# TPL5111_breakout.net
KiCad netlist of a schematic drawn in EAGLE
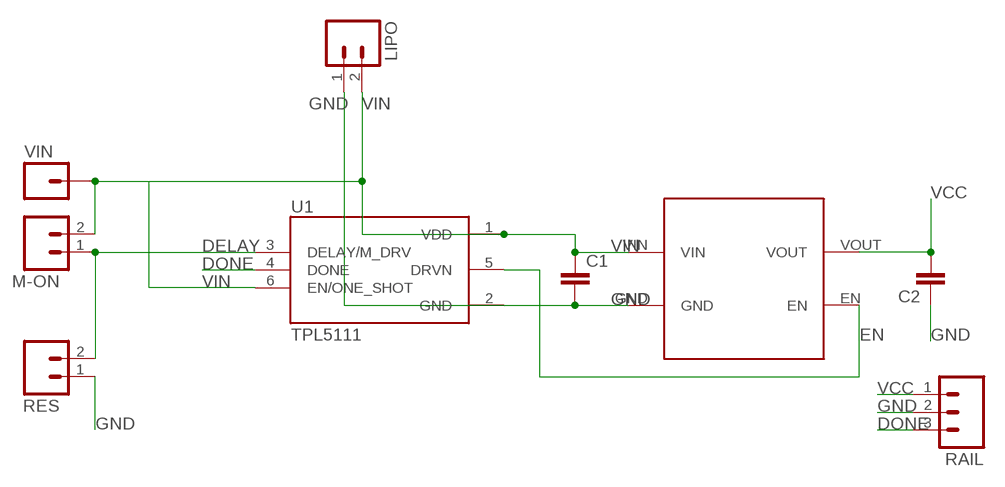
[diagram p0: schematic, sheet 1]

(export (version "E")
  (design (tool "Eeschema 10.0.6"))
  (components
    (comp (ref "C1")
      (value "CAP0603-CAP")
      (footprint "eagle-import:0603-CAP")
      (libsource (lib "eagle-import") (part "CAP0603-CAP"))
    )
    (comp (ref "C2")
      (value "CAP0603-CAP")
      (footprint "eagle-import:0603-CAP")
      (libsource (lib "eagle-import") (part "CAP0603-CAP"))
    )
    (comp (ref "LIPO")
      (value "M02PTH")
      (footprint "eagle-import:1X02")
      (libsource (lib "eagle-import") (part "M02PTH"))
    )
    (comp (ref "M-ON")
      (value "M02PTH")
      (footprint "eagle-import:1X02")
      (libsource (lib "eagle-import") (part "M02PTH"))
    )
    (comp (ref "RAIL")
      (value "M03PTH")
      (footprint "eagle-import:1X03")
      (libsource (lib "eagle-import") (part "M03PTH"))
    )
    (comp (ref "RES")
      (value "M02PTH")
      (footprint "eagle-import:1X02")
      (libsource (lib "eagle-import") (part "M02PTH"))
    )
    (comp (ref "U$2")
      (value "AP2112K")
      (footprint "eagle-import:AP2112K-SOT23-5")
      (libsource (lib "eagle-import") (part "AP2112K"))
    )
    (comp (ref "U1")
      (value "TPL5111")
      (footprint "eagle-import:SOT95P280X110-6N")
      (fields (field (name "MF") "Texas Instruments") (field (name "MP") "TPL5111DDCR"))
      (libsource (lib "eagle-import") (part "TPL5111DDCR"))
    )
    (comp (ref "VIN")
      (value "M01PTH")
      (footprint "eagle-import:1X01")
      (libsource (lib "eagle-import") (part "M01PTH"))
    )
  )
  (nets
    (net (code "1") (name "/DELAY") (class "Default")
      (node (ref "M-ON") (pin "1") (pinfunction "1_1") (pintype "passive"))
      (node (ref "RES") (pin "2") (pinfunction "2_2") (pintype "passive"))
      (node (ref "U1") (pin "3") (pinfunction "DELAY/M_DRV_3") (pintype "input"))
    )
    (net (code "2") (name "/DONE") (class "Default")
      (node (ref "RAIL") (pin "3") (pinfunction "3_3") (pintype "passive"))
      (node (ref "U1") (pin "4") (pinfunction "DONE_4") (pintype "input"))
    )
    (net (code "3") (name "/EN") (class "Default")
      (node (ref "U$2") (pin "EN") (pinfunction "EN_EN") (pintype "bidirectional"))
      (node (ref "U1") (pin "5") (pinfunction "DRVN_5") (pintype "output"))
    )
    (net (code "4") (name "/GND") (class "Default")
      (node (ref "C1") (pin "2") (pinfunction "2_2") (pintype "passive"))
      (node (ref "C2") (pin "1") (pinfunction "1_1") (pintype "passive"))
      (node (ref "LIPO") (pin "1") (pinfunction "1_1") (pintype "passive"))
      (node (ref "RAIL") (pin "2") (pinfunction "2_2") (pintype "passive"))
      (node (ref "RES") (pin "1") (pinfunction "1_1") (pintype "passive"))
      (node (ref "U$2") (pin "GND") (pinfunction "GND_GND") (pintype "bidirectional"))
      (node (ref "U1") (pin "2") (pinfunction "GND_2") (pintype "power_in"))
    )
    (net (code "5") (name "/VCC") (class "Default")
      (node (ref "C2") (pin "2") (pinfunction "2_2") (pintype "passive"))
      (node (ref "RAIL") (pin "1") (pinfunction "1_1") (pintype "passive"))
      (node (ref "U$2") (pin "VOUT") (pinfunction "VOUT_VOUT") (pintype "bidirectional"))
    )
    (net (code "6") (name "/VIN") (class "Default")
      (node (ref "C1") (pin "1") (pinfunction "1_1") (pintype "passive"))
      (node (ref "LIPO") (pin "2") (pinfunction "2_2") (pintype "passive"))
      (node (ref "M-ON") (pin "2") (pinfunction "2_2") (pintype "passive"))
      (node (ref "U$2") (pin "VIN") (pinfunction "VIN_VIN") (pintype "bidirectional"))
      (node (ref "U1") (pin "1") (pinfunction "VDD_1") (pintype "power_in"))
      (node (ref "U1") (pin "6") (pinfunction "EN/ONE_SHOT_6") (pintype "input"))
      (node (ref "VIN") (pin "1") (pinfunction "1_1") (pintype "passive"))
    )
  )
)
